# SX1280_MID_VELOCITY.net
KiCad netlist of a schematic drawn in Altium Designer
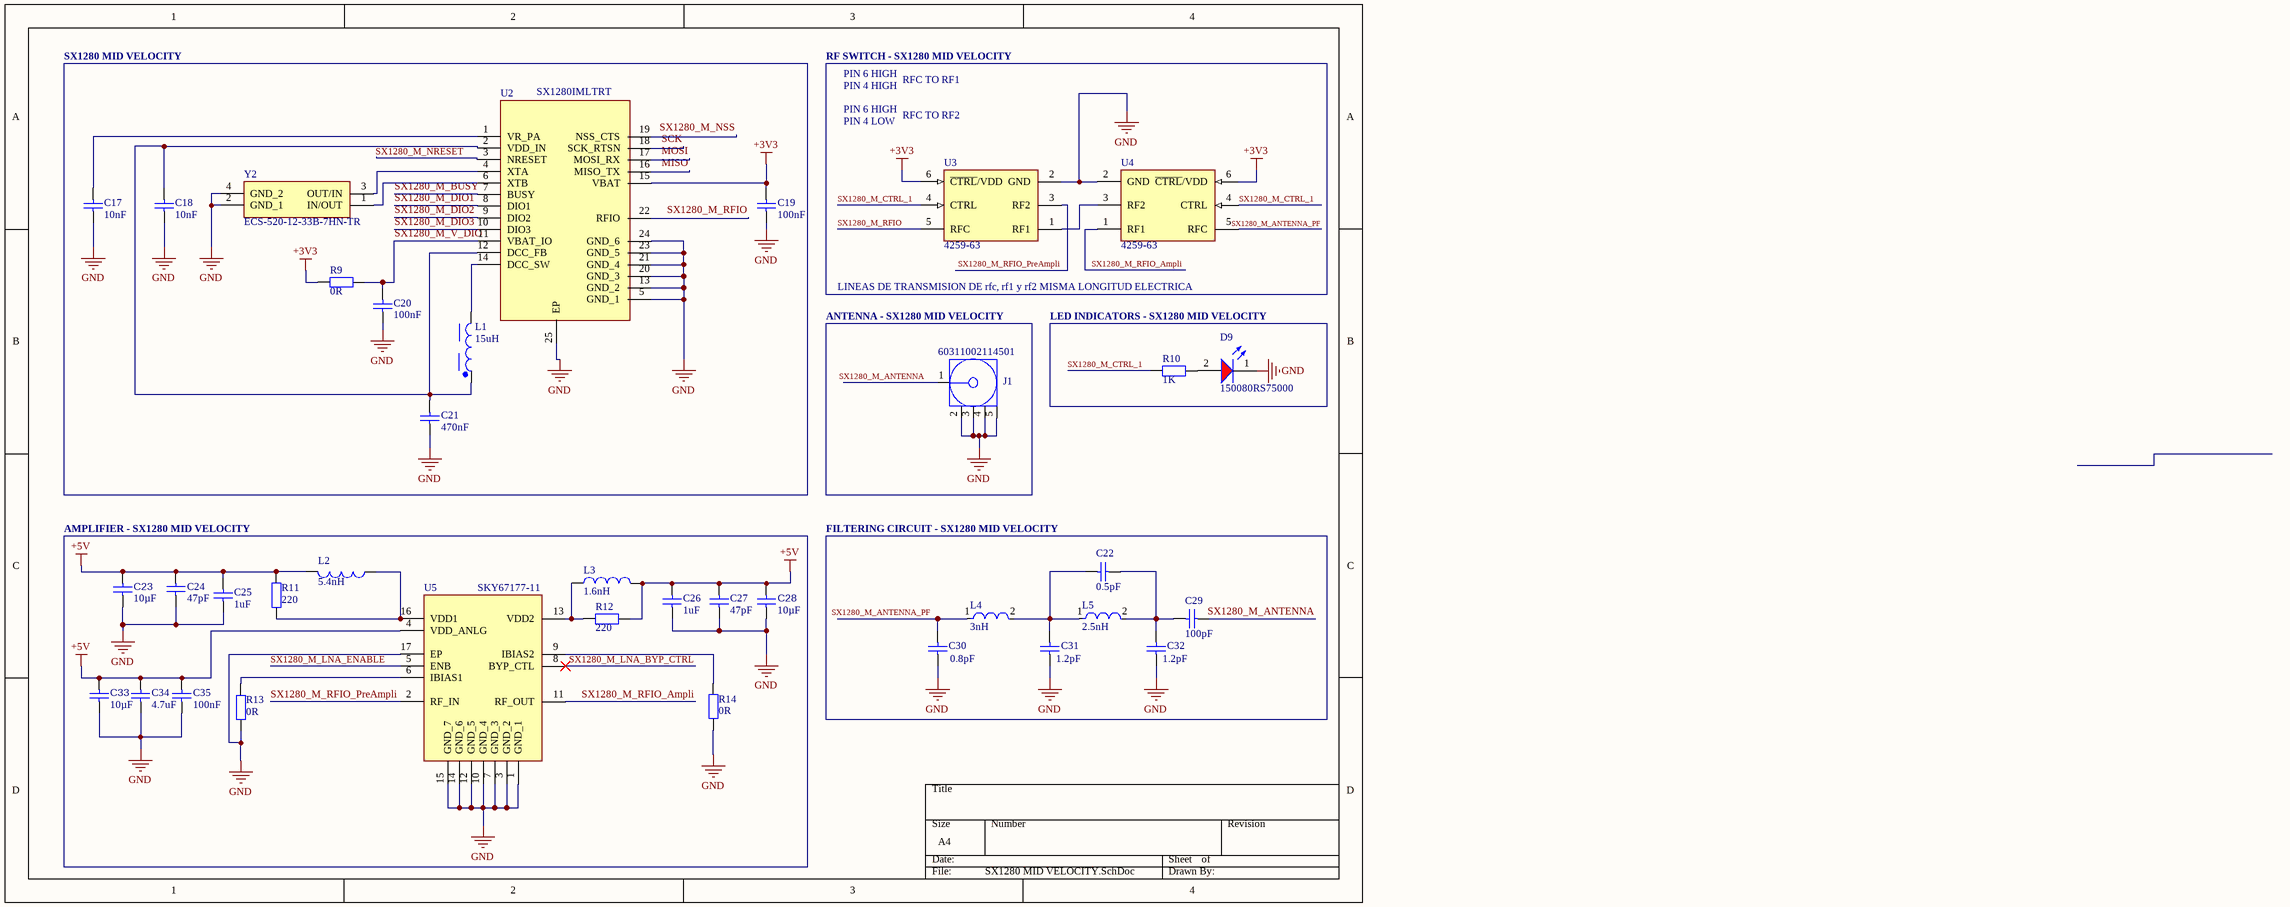
[diagram p0: SX1280 MID VELOCITY.SchDoc]

(export (version "E")
  (design (tool "Eeschema 10.0.6"))
  (components
    (comp (ref "C17")
      (value "10nF")
      (footprint "WCAP-CSGP_0603_L1.6W0.8H0.8_Reflow")
      (description "WCAP-CSGP Multilayer Ceramic Chip Capacitor, General Purpose, size 0603, X7R, 10nF, 25VDC")
      (fields
        (field (name "MANUFACTURER") "Wurth Elektronik")
        (field (name "MANUFACTURER PART NUMBER") "885012206065")
      )
      (libsource (lib "LEEM UPM") (part "885012209047R"))
    )
    (comp (ref "C18")
      (value "10nF")
      (footprint "WCAP-CSGP_0603_L1.6W0.8H0.8_Reflow")
      (description "WCAP-CSGP Multilayer Ceramic Chip Capacitor, General Purpose, size 0603, X7R, 10nF, 25VDC")
      (fields
        (field (name "MANUFACTURER") "Wurth Elektronik")
        (field (name "MANUFACTURER PART NUMBER") "885012206065")
      )
      (libsource (lib "LEEM UPM") (part "885012209047R"))
    )
    (comp (ref "C19")
      (value "100nF")
      (footprint "WCAP-CSGP_0603_L1.6W0.8H0.8_Reflow")
      (description "WCAP-CSGP Multilayer Ceramic Chip Capacitor, General Purpose, size 0603, X7R, 100nF, 25VDC")
      (fields
        (field (name "MANUFACTURER") "Wurth Elektronik")
        (field (name "MANUFACTURER PART NUMBER") "885012206071")
      )
      (libsource (lib "LEEM UPM") (part "885012209047R"))
    )
    (comp (ref "C20")
      (value "100nF")
      (footprint "WCAP-CSGP_0603_L1.6W0.8H0.8_Reflow")
      (description "WCAP-CSGP Multilayer Ceramic Chip Capacitor, General Purpose, size 0603, X7R, 100nF, 25VDC")
      (fields
        (field (name "MANUFACTURER") "Wurth Elektronik")
        (field (name "MANUFACTURER PART NUMBER") "885012206071")
      )
      (libsource (lib "LEEM UPM") (part "885012209047R"))
    )
    (comp (ref "C21")
      (value "470nF")
      (footprint "WCAP-CSGP_0603_L1.6W0.8H0.8_Reflow")
      (description "WCAP-CSGP Multilayer Ceramic Chip Capacitor, General Purpose, size 0603, X7R, 470nF, 16VDC")
      (fields
        (field (name "MANUFACTURER PART NUMBER") "885012206050")
        (field (name "MANUFACTURER") "Wurth Elektronik")
      )
      (libsource (lib "LEEM UPM") (part "885012209047R"))
    )
    (comp (ref "C22")
      (value "0.5pF")
      (footprint "WCAP-CSGP_0603_L1.6W0.8H0.8_Reflow")
      (description "WCAP-CSGP Multilayer Ceramic Chip Capacitor, General Purpose, size 0603, NP0, 0.5pF, 100VDC")
      (fields
        (field (name "MANUFACTURER") "Wurth Elektronik")
        (field (name "MANUFACTURER PART NUMBER") "885012006086")
      )
      (libsource (lib "LEEM UPM") (part "885012209047R"))
    )
    (comp (ref "C23")
      (value "10µF")
      (footprint "GRM21BR61E106KA73K-Footprint-1")
      (fields (field (name "Comment") "GRM21BR61E106KA73K"))
      (libsource (lib "LEEM UPM") (part "CAP-NP-2"))
    )
    (comp (ref "C24")
      (value "47pF")
      (footprint "WCAP-CSGP_0603_L1.6W0.8H0.8_Reflow")
      (description "WCAP-CSGP Multilayer Ceramic Chip Capacitor, General Purpose, size 0603, NP0, 47pF, 25VDC")
      (fields
        (field (name "MANUFACTURER") "Wurth Elektronik")
        (field (name "MANUFACTURER PART NUMBER") "885012006036")
      )
      (libsource (lib "LEEM UPM") (part "885012209047R"))
    )
    (comp (ref "C25")
      (value "1uF")
      (footprint "WCAP-CSGP_0603_L1.6W0.8H0.8_Reflow")
      (description "WCAP-CSGP Multilayer Ceramic Chip Capacitor, General Purpose, size 0603, X7R, 1uF, 16VDC")
      (fields
        (field (name "MANUFACTURER") "Wurth Elektronik")
        (field (name "MANUFACTURER PART NUMBER") "885012206052")
      )
      (libsource (lib "LEEM UPM") (part "885012209047R"))
    )
    (comp (ref "C26")
      (value "1uF")
      (footprint "WCAP-CSGP_0603_L1.6W0.8H0.8_Reflow")
      (description "WCAP-CSGP Multilayer Ceramic Chip Capacitor, General Purpose, size 0603, X7R, 1uF, 16VDC")
      (fields
        (field (name "MANUFACTURER") "Wurth Elektronik")
        (field (name "MANUFACTURER PART NUMBER") "885012206052")
      )
      (libsource (lib "LEEM UPM") (part "885012209047R"))
    )
    (comp (ref "C27")
      (value "47pF")
      (footprint "WCAP-CSGP_0603_L1.6W0.8H0.8_Reflow")
      (description "WCAP-CSGP Multilayer Ceramic Chip Capacitor, General Purpose, size 0603, NP0, 47pF, 25VDC")
      (fields
        (field (name "MANUFACTURER") "Wurth Elektronik")
        (field (name "MANUFACTURER PART NUMBER") "885012006036")
      )
      (libsource (lib "LEEM UPM") (part "885012209047R"))
    )
    (comp (ref "C28")
      (value "10µF")
      (footprint "GRM21BR61E106KA73K-Footprint-1")
      (fields (field (name "Comment") "GRM21BR61E106KA73K"))
      (libsource (lib "LEEM UPM") (part "CAP-NP-2"))
    )
    (comp (ref "C29")
      (value "100pF")
      (footprint "WCAP-CSGP_0603_L1.6W0.8H0.8_Reflow")
      (description "WCAP-CSGP Multilayer Ceramic Chip Capacitor, General Purpose, size 0603, NP0, 100pF, 50VDC")
      (fields
        (field (name "MANUFACTURER") "Wurth Elektronik")
        (field (name "MANUFACTURER PART NUMBER") "885012006057")
      )
      (libsource (lib "LEEM UPM") (part "885012209047R"))
    )
    (comp (ref "C30")
      (value "0.8pF")
      (footprint "WCAP-CSGP_0603_L1.6W0.8H0.8_Reflow")
      (description "Multilayer Ceramic Chip Capacitor, General Purpose, size 0603, X7R, 0.8pF, 50VDC, Tol=0.1pF")
      (fields
        (field (name "MANUFACTURER") "TAIYO YUDEN")
        (field (name "MANUFACTURER PART NUMBER") "MBASU063SCK0R8BFNA01")
      )
      (libsource (lib "LEEM UPM") (part "885012209047R"))
    )
    (comp (ref "C31")
      (value "1.2pF")
      (footprint "WCAP-CSGP_0603_L1.6W0.8H0.8_Reflow")
      (description "Multilayer Ceramic Chip Capacitor, General Purpose, size 0603, X7R, 1.2pF, 50VDC, Tol=0.1pF")
      (fields
        (field (name "MANUFACTURER") "KYOCERA AVX")
        (field (name "MANUFACTURER PART NUMBER") "06035A1R2B4T2A")
      )
      (libsource (lib "LEEM UPM") (part "885012209047R"))
    )
    (comp (ref "C32")
      (value "1.2pF")
      (footprint "WCAP-CSGP_0603_L1.6W0.8H0.8_Reflow")
      (description "Multilayer Ceramic Chip Capacitor, General Purpose, size 0603, X7R, 1.2pF, 50VDC, Tol=0.1pF")
      (fields
        (field (name "MANUFACTURER") "KYOCERA AVX")
        (field (name "MANUFACTURER PART NUMBER") "06035A1R2B4T2A")
      )
      (libsource (lib "LEEM UPM") (part "885012209047R"))
    )
    (comp (ref "C33")
      (value "10µF")
      (footprint "GRM21BR61E106KA73K-Footprint-1")
      (fields (field (name "Comment") "GRM21BR61E106KA73K"))
      (libsource (lib "LEEM UPM") (part "CAP-NP-2"))
    )
    (comp (ref "C34")
      (value "4.7uF")
      (footprint "WCAP-CSGP_0603_L1.6W0.8H0.8_Reflow")
      (description "WCAP-CSGP Multilayer Ceramic Chip Capacitor, General Purpose, size 0603, X5R, 4.7uF, 10VDC")
      (fields
        (field (name "MANUFACTURER PART NUMBER") "885012106012")
        (field (name "MANUFACTURER") "Wurth Elektronik")
      )
      (libsource (lib "LEEM UPM") (part "885012209047R"))
    )
    (comp (ref "C35")
      (value "100nF")
      (footprint "WCAP-CSGP_0603_L1.6W0.8H0.8_Reflow")
      (description "WCAP-CSGP Multilayer Ceramic Chip Capacitor, General Purpose, size 0603, X7R, 100nF, 25VDC")
      (fields
        (field (name "MANUFACTURER") "Wurth Elektronik")
        (field (name "MANUFACTURER PART NUMBER") "885012206071")
      )
      (libsource (lib "LEEM UPM") (part "885012209047R"))
    )
    (comp (ref "D9")
      (value "150080RS75000")
      (footprint "WL-SMCW_0805_150080xx75000")
      (description "WL-SMCW Mono-color Chip LED Waterclear, SMT, size 0805, Red, 2V, 140°")
      (fields (field (name "MANUFACTURER") "Wurth Elektronik"))
      (libsource (lib "LEEM UPM") (part "150120SS75000"))
    )
    (comp (ref "J1")
      (value "60311002114501")
      (footprint "60311002114501")
      (description "60311002114501 Rf Coax Conn, Sma R/A Jack, 50 Ohm, Pcb Rohs Compliant: Yes")
      (libsource (lib "Altium Content Vault") (part "Jack_4GND"))
    )
    (comp (ref "L1")
      (value "784373460150")
      (footprint "WE-LHCA_7030")
      (description "WE-LHCA Low Profile High Current Inductor, SMT, size 7030, 15uH, 3A")
      (fields (field (name "INDUCTANCE") "15uH") (field (name "MANUFACTURER") "Wurth Elektronik"))
      (libsource (lib "LEEM UPM") (part "7843734600068"))
    )
    (comp (ref "L2")
      (value "5.4nH")
      (footprint "WE-KI_0603")
      (description "744761056A Wirewound Inductor, 5.6Nh, 0.7A, 0603 Rohs Compliant: Yes")
      (libsource (lib "Altium Content Vault") (part "Inductor - 1"))
    )
    (comp (ref "L3")
      (value "1.6nH")
      (footprint "WE-KI_0603")
      (description "744761016A WE-KI SMT Wire Wound Ceramic Inductor")
      (libsource (lib "Altium Content Vault") (part "Inductor - 1"))
    )
    (comp (ref "L4")
      (value "3nH")
      (footprint "FP-LQW18AN_80-MFG")
      (description "Wire Wound RF Inductor 3nH ±0.2nH 670mA 0.17Ω 0603 (1608)")
      (libsource (lib "Altium Content Vault") (part "725321dda6339637d4d059423bc1c3c"))
    )
    (comp (ref "L5")
      (value "2.5nH")
      (footprint "FP-LQW18AN_80-MFG")
      (description "Wire Wound RF Inductor 2.4nH ±0.2nH 2400mA 0.026Ω 0603 (1608)")
      (libsource (lib "Altium Content Vault") (part "725321dda6339637d4d059423bc1c3c"))
    )
    (comp (ref "R9")
      (value "0R")
      (footprint "WRIS-RSKS_0603_Reflow")
      (description "WRIS-RSKS Thick Film Resistor, size 0603, 100mW")
      (fields
        (field (name "MANUFACTURER") "Wurth Elektronik")
        (field (name "MANUFACTURER PART NUMBER") "560112116001")
      )
      (libsource (lib "LEEM UPM") (part "560112140010"))
    )
    (comp (ref "R10")
      (value "1K")
      (footprint "WRIS-RSKS_0603_Reflow")
      (description "WRIS-RSKS Thick Film Resistor, size 0603, 1000Ohm, 100mW")
      (fields
        (field (name "MANUFACTURER PART NUMBER") "560112116014")
        (field (name "MANUFACTURER") "Wurth Elektronik")
      )
      (libsource (lib "") (part "560112140010_2"))
    )
    (comp (ref "R11")
      (value "220")
      (footprint "WRIS-RSKS_0603_Reflow")
      (description "WRIS-RSKS Thick Film Resistor, size 0603, 220Ohm, 100mW")
      (fields
        (field (name "MANUFACTURER PART NUMBER") "560112116126")
        (field (name "MANUFACTURER") "Wurth Elektronik")
      )
      (libsource (lib "") (part "560112140010_1"))
    )
    (comp (ref "R12")
      (value "220")
      (footprint "WRIS-RSKS_0603_Reflow")
      (description "WRIS-RSKS Thick Film Resistor, size 0603, 220Ohm, 100mW")
      (fields
        (field (name "MANUFACTURER PART NUMBER") "560112116126")
        (field (name "MANUFACTURER") "Wurth Elektronik")
      )
      (libsource (lib "") (part "560112140010_2"))
    )
    (comp (ref "R13")
      (value "0R")
      (footprint "WRIS-RSKS_0603_Reflow")
      (description "WRIS-RSKS Thick Film Resistor, size 0603, 100mW")
      (fields
        (field (name "MANUFACTURER") "Wurth Elektronik")
        (field (name "MANUFACTURER PART NUMBER") "560112116001")
      )
      (libsource (lib "") (part "560112140010_1"))
    )
    (comp (ref "R14")
      (value "0R")
      (footprint "WRIS-RSKS_0603_Reflow")
      (description "WRIS-RSKS Thick Film Resistor, size 0603, 100mW")
      (fields
        (field (name "MANUFACTURER") "Wurth Elektronik")
        (field (name "MANUFACTURER PART NUMBER") "560112116001")
      )
      (libsource (lib "") (part "560112140010_1"))
    )
    (comp (ref "U2")
      (value "SX1280IMLTRT")
      (footprint "SX1280IMLTRT-Footprint-1")
      (description "Telecom Circuit")
      (libsource (lib "LEEM UPM") (part "SX1280IMLTRT"))
    )
    (comp (ref "U3")
      (value "4259-63")
      (footprint "PERE-SC-70-6_M")
      (description "IC RF Switch SPDT, 50 Ohm, 6-Pin SC70, RoHS, Tape and Reel")
      (fields (field (name "MANUFACTURER") "Peregrine Semiconductor"))
      (libsource (lib "Altium Content Vault") (part "PERE-PE4259-6"))
    )
    (comp (ref "U4")
      (value "4259-63")
      (footprint "PERE-SC-70-6_M")
      (description "IC RF Switch SPDT, 50 Ohm, 6-Pin SC70, RoHS, Tape and Reel")
      (fields (field (name "MANUFACTURER") "Peregrine Semiconductor"))
      (libsource (lib "") (part "PERE-PE4259-6_1"))
    )
    (comp (ref "U5")
      (value "SKY67177-11")
      (footprint "SKY67177-11-Footprint-1")
      (description "Amplificador de RF High Gain LNA")
      (libsource (lib "LEEM UPM") (part "SKY67177-11-Symbol-1"))
    )
    (comp (ref "Y2")
      (value "ECS-520-12-33B-7HN-TR")
      (footprint "ECS-520-12-33B-7HN-TR-Footprint-1")
      (description "Crystals 52.000 MHz 12 pF ECS-33B +/-7/15 ppm -40 - +85C +/-1 ppm Aging 3225 4-SMD RoHS")
      (libsource (lib "LEEM UPM") (part "ECS-520-12-33B-7HN-TR"))
    )
  )
  (nets
    (net (code "1") (name "+3V3") (class "Default")
      (node (ref "C19") (pin "2") (pinfunction "2_2") (pintype "passive"))
      (node (ref "R9") (pin "2") (pinfunction "2_2") (pintype "passive"))
      (node (ref "U2") (pin "15") (pinfunction "VBAT_15") (pintype "passive"))
      (node (ref "U3") (pin "6") (pinfunction "~{CTRL}/VDD_6") (pintype "input"))
      (node (ref "U4") (pin "6") (pinfunction "~{CTRL}/VDD_6") (pintype "input"))
    )
    (net (code "2") (name "+5V") (class "Default")
      (node (ref "C23") (pin "2") (pinfunction "2_2") (pintype "passive"))
      (node (ref "C24") (pin "1") (pinfunction "1_1") (pintype "passive"))
      (node (ref "C25") (pin "2") (pinfunction "2_2") (pintype "passive"))
      (node (ref "C26") (pin "2") (pinfunction "2_2") (pintype "passive"))
      (node (ref "C27") (pin "1") (pinfunction "1_1") (pintype "passive"))
      (node (ref "C28") (pin "2") (pinfunction "2_2") (pintype "passive"))
      (node (ref "C33") (pin "2") (pinfunction "2_2") (pintype "passive"))
      (node (ref "C34") (pin "2") (pinfunction "2_2") (pintype "passive"))
      (node (ref "C35") (pin "2") (pinfunction "2_2") (pintype "passive"))
      (node (ref "L2") (pin "2") (pinfunction "2_2") (pintype "passive"))
      (node (ref "L3") (pin "2") (pinfunction "2_2") (pintype "passive"))
      (node (ref "R11") (pin "2") (pinfunction "2_2") (pintype "passive"))
      (node (ref "R12") (pin "2") (pinfunction "2_2") (pintype "passive"))
      (node (ref "U5") (pin "4") (pinfunction "VDD_ANLG_4") (pintype "passive"))
    )
    (net (code "3") (name "/MISO") (class "Default")
      (node (ref "U2") (pin "16") (pinfunction "MISO_TX_16") (pintype "passive"))
    )
    (net (code "4") (name "/MOSI") (class "Default")
      (node (ref "U2") (pin "17") (pinfunction "MOSI_RX_17") (pintype "passive"))
    )
    (net (code "5") (name "/SCK") (class "Default")
      (node (ref "U2") (pin "18") (pinfunction "SCK_RTSN_18") (pintype "passive"))
    )
    (net (code "6") (name "/SX1280_M_ANTENNA") (class "Default")
      (node (ref "C29") (pin "2") (pinfunction "2_2") (pintype "passive"))
      (node (ref "J1") (pin "1") (pinfunction "Signal_1") (pintype "passive"))
    )
    (net (code "7") (name "/SX1280_M_ANTENNA_PF") (class "Default")
      (node (ref "C30") (pin "2") (pinfunction "2_2") (pintype "passive"))
      (node (ref "L4") (pin "1") (pinfunction "1_1") (pintype "passive"))
      (node (ref "U4") (pin "5") (pinfunction "RFC_5") (pintype "passive"))
    )
    (net (code "8") (name "/SX1280_M_BUSY") (class "Default")
      (node (ref "U2") (pin "7") (pinfunction "BUSY_7") (pintype "passive"))
    )
    (net (code "9") (name "/SX1280_M_CTRL_1") (class "Default")
      (node (ref "R10") (pin "1") (pinfunction "1_1") (pintype "passive"))
      (node (ref "U3") (pin "4") (pinfunction "CTRL_4") (pintype "input"))
      (node (ref "U4") (pin "4") (pinfunction "CTRL_4") (pintype "input"))
    )
    (net (code "10") (name "/SX1280_M_DIO1") (class "Default")
      (node (ref "U2") (pin "8") (pinfunction "DIO1_8") (pintype "passive"))
    )
    (net (code "11") (name "/SX1280_M_DIO2") (class "Default")
      (node (ref "U2") (pin "9") (pinfunction "DIO2_9") (pintype "passive"))
    )
    (net (code "12") (name "/SX1280_M_DIO3") (class "Default")
      (node (ref "U2") (pin "10") (pinfunction "DIO3_10") (pintype "passive"))
    )
    (net (code "13") (name "/SX1280_M_LNA_BYP_CTRL") (class "Default")
      (node (ref "U5") (pin "8") (pinfunction "BYP_CTL_8") (pintype "passive+no_connect"))
    )
    (net (code "14") (name "/SX1280_M_LNA_ENABLE") (class "Default")
      (node (ref "U5") (pin "5") (pinfunction "ENB_5") (pintype "passive"))
    )
    (net (code "15") (name "/SX1280_M_NRESET") (class "Default")
      (node (ref "U2") (pin "3") (pinfunction "NRESET_3") (pintype "passive"))
    )
    (net (code "16") (name "/SX1280_M_NSS") (class "Default")
      (node (ref "U2") (pin "19") (pinfunction "NSS_CTS_19") (pintype "passive"))
    )
    (net (code "17") (name "/SX1280_M_RFIO") (class "Default")
      (node (ref "U2") (pin "22") (pinfunction "RFIO_22") (pintype "passive"))
      (node (ref "U3") (pin "5") (pinfunction "RFC_5") (pintype "passive"))
    )
    (net (code "18") (name "/SX1280_M_RFIO_Ampli") (class "Default")
      (node (ref "U4") (pin "1") (pinfunction "RF1_1") (pintype "passive"))
      (node (ref "U5") (pin "11") (pinfunction "RF_OUT_11") (pintype "passive"))
    )
    (net (code "19") (name "/SX1280_M_RFIO_PreAmpli") (class "Default")
      (node (ref "U3") (pin "3") (pinfunction "RF2_3") (pintype "passive"))
      (node (ref "U5") (pin "2") (pinfunction "RF_IN_2") (pintype "passive"))
    )
    (net (code "20") (name "/SX1280_M_V_DIO") (class "Default")
      (node (ref "C20") (pin "2") (pinfunction "2_2") (pintype "passive"))
      (node (ref "R9") (pin "1") (pinfunction "1_1") (pintype "passive"))
      (node (ref "U2") (pin "11") (pinfunction "VBAT_IO_11") (pintype "passive"))
    )
    (net (code "21") (name "GND") (class "Default")
      (node (ref "C17") (pin "1") (pinfunction "1_1") (pintype "passive"))
      (node (ref "C18") (pin "1") (pinfunction "1_1") (pintype "passive"))
      (node (ref "C19") (pin "1") (pinfunction "1_1") (pintype "passive"))
      (node (ref "C20") (pin "1") (pinfunction "1_1") (pintype "passive"))
      (node (ref "C21") (pin "1") (pinfunction "1_1") (pintype "passive"))
      (node (ref "C23") (pin "1") (pinfunction "1_1") (pintype "passive"))
      (node (ref "C24") (pin "2") (pinfunction "2_2") (pintype "passive"))
      (node (ref "C25") (pin "1") (pinfunction "1_1") (pintype "passive"))
      (node (ref "C26") (pin "1") (pinfunction "1_1") (pintype "passive"))
      (node (ref "C27") (pin "2") (pinfunction "2_2") (pintype "passive"))
      (node (ref "C28") (pin "1") (pinfunction "1_1") (pintype "passive"))
      (node (ref "C30") (pin "1") (pinfunction "1_1") (pintype "passive"))
      (node (ref "C31") (pin "1") (pinfunction "1_1") (pintype "passive"))
      (node (ref "C32") (pin "1") (pinfunction "1_1") (pintype "passive"))
      (node (ref "C33") (pin "1") (pinfunction "1_1") (pintype "passive"))
      (node (ref "C34") (pin "1") (pinfunction "1_1") (pintype "passive"))
      (node (ref "C35") (pin "1") (pinfunction "1_1") (pintype "passive"))
      (node (ref "D9") (pin "1") (pinfunction "K_1") (pintype "passive"))
      (node (ref "J1") (pin "2") (pinfunction "GND_2") (pintype "passive"))
      (node (ref "J1") (pin "3") (pinfunction "GND_3") (pintype "passive"))
      (node (ref "J1") (pin "4") (pinfunction "GND_4") (pintype "passive"))
      (node (ref "J1") (pin "5") (pinfunction "GND_5") (pintype "passive"))
      (node (ref "R13") (pin "1") (pinfunction "1_1") (pintype "passive"))
      (node (ref "R14") (pin "1") (pinfunction "1_1") (pintype "passive"))
      (node (ref "U2") (pin "13") (pinfunction "GND_2_13") (pintype "passive"))
      (node (ref "U2") (pin "20") (pinfunction "GND_3_20") (pintype "passive"))
      (node (ref "U2") (pin "21") (pinfunction "GND_4_21") (pintype "passive"))
      (node (ref "U2") (pin "23") (pinfunction "GND_5_23") (pintype "passive"))
      (node (ref "U2") (pin "24") (pinfunction "GND_6_24") (pintype "passive"))
      (node (ref "U2") (pin "25") (pinfunction "EP_25") (pintype "passive"))
      (node (ref "U2") (pin "5") (pinfunction "GND_1_5") (pintype "passive"))
      (node (ref "U3") (pin "2") (pinfunction "GND_2") (pintype "power_in"))
      (node (ref "U4") (pin "2") (pinfunction "GND_2") (pintype "power_in"))
      (node (ref "U5") (pin "1") (pinfunction "GND_1_1") (pintype "passive"))
      (node (ref "U5") (pin "10") (pinfunction "GND_4_10") (pintype "passive"))
      (node (ref "U5") (pin "12") (pinfunction "GND_5_12") (pintype "passive"))
      (node (ref "U5") (pin "14") (pinfunction "GND_6_14") (pintype "passive"))
      (node (ref "U5") (pin "15") (pinfunction "GND_7_15") (pintype "passive"))
      (node (ref "U5") (pin "17") (pinfunction "EP_17") (pintype "passive"))
      (node (ref "U5") (pin "3") (pinfunction "GND_2_3") (pintype "passive"))
      (node (ref "U5") (pin "7") (pinfunction "GND_3_7") (pintype "passive"))
      (node (ref "Y2") (pin "2") (pinfunction "GND_1_2") (pintype "passive"))
      (node (ref "Y2") (pin "4") (pinfunction "GND_2_4") (pintype "passive"))
    )
    (net (code "22") (name "Net-(C22-Pad1)") (class "Default")
      (node (ref "C22") (pin "1") (pinfunction "1_1") (pintype "passive"))
      (node (ref "C31") (pin "2") (pinfunction "2_2") (pintype "passive"))
      (node (ref "L4") (pin "2") (pinfunction "2_2") (pintype "passive"))
      (node (ref "L5") (pin "1") (pinfunction "1_1") (pintype "passive"))
    )
    (net (code "23") (name "Net-(C22-Pad2)") (class "Default")
      (node (ref "C22") (pin "2") (pinfunction "2_2") (pintype "passive"))
      (node (ref "C29") (pin "1") (pinfunction "1_1") (pintype "passive"))
      (node (ref "C32") (pin "2") (pinfunction "2_2") (pintype "passive"))
      (node (ref "L5") (pin "2") (pinfunction "2_2") (pintype "passive"))
    )
    (net (code "24") (name "Net-(D9-A)") (class "Default")
      (node (ref "D9") (pin "2") (pinfunction "A_2") (pintype "passive"))
      (node (ref "R10") (pin "2") (pinfunction "2_2") (pintype "passive"))
    )
    (net (code "25") (name "Net-(U2-DCC_FB)") (class "Default")
      (node (ref "C18") (pin "2") (pinfunction "2_2") (pintype "passive"))
      (node (ref "C21") (pin "2") (pinfunction "2_2") (pintype "passive"))
      (node (ref "L1") (pin "1") (pinfunction "1_1") (pintype "passive"))
      (node (ref "U2") (pin "12") (pinfunction "DCC_FB_12") (pintype "passive"))
      (node (ref "U2") (pin "2") (pinfunction "VDD_IN_2") (pintype "passive"))
    )
    (net (code "26") (name "Net-(U2-DCC_SW)") (class "Default")
      (node (ref "L1") (pin "2") (pinfunction "2_2") (pintype "passive"))
      (node (ref "U2") (pin "14") (pinfunction "DCC_SW_14") (pintype "passive"))
    )
    (net (code "27") (name "Net-(U2-VR_PA)") (class "Default")
      (node (ref "C17") (pin "2") (pinfunction "2_2") (pintype "passive"))
      (node (ref "U2") (pin "1") (pinfunction "VR_PA_1") (pintype "passive"))
    )
    (net (code "28") (name "Net-(U2-XTA)") (class "Default")
      (node (ref "U2") (pin "4") (pinfunction "XTA_4") (pintype "passive"))
      (node (ref "Y2") (pin "3") (pinfunction "OUT/IN_3") (pintype "passive"))
    )
    (net (code "29") (name "Net-(U2-XTB)") (class "Default")
      (node (ref "U2") (pin "6") (pinfunction "XTB_6") (pintype "passive"))
      (node (ref "Y2") (pin "1") (pinfunction "IN/OUT_1") (pintype "passive"))
    )
    (net (code "30") (name "Net-(U3-RF1)") (class "Default")
      (node (ref "U3") (pin "1") (pinfunction "RF1_1") (pintype "passive"))
      (node (ref "U4") (pin "3") (pinfunction "RF2_3") (pintype "passive"))
    )
    (net (code "31") (name "Net-(U5-IBIAS1)") (class "Default")
      (node (ref "R13") (pin "2") (pinfunction "2_2") (pintype "passive"))
      (node (ref "U5") (pin "6") (pinfunction "IBIAS1_6") (pintype "passive"))
    )
    (net (code "32") (name "Net-(U5-IBIAS2)") (class "Default")
      (node (ref "R14") (pin "2") (pinfunction "2_2") (pintype "passive"))
      (node (ref "U5") (pin "9") (pinfunction "IBIAS2_9") (pintype "passive"))
    )
    (net (code "33") (name "Net-(U5-VDD1)") (class "Default")
      (node (ref "L2") (pin "1") (pinfunction "1_1") (pintype "passive"))
      (node (ref "R11") (pin "1") (pinfunction "1_1") (pintype "passive"))
      (node (ref "U5") (pin "16") (pinfunction "VDD1_16") (pintype "passive"))
    )
    (net (code "34") (name "Net-(U5-VDD2)") (class "Default")
      (node (ref "L3") (pin "1") (pinfunction "1_1") (pintype "passive"))
      (node (ref "R12") (pin "1") (pinfunction "1_1") (pintype "passive"))
      (node (ref "U5") (pin "13") (pinfunction "VDD2_13") (pintype "passive"))
    )
  )
)
